# 04_MCU.net
KiCad netlist of a schematic drawn in Altium Designer
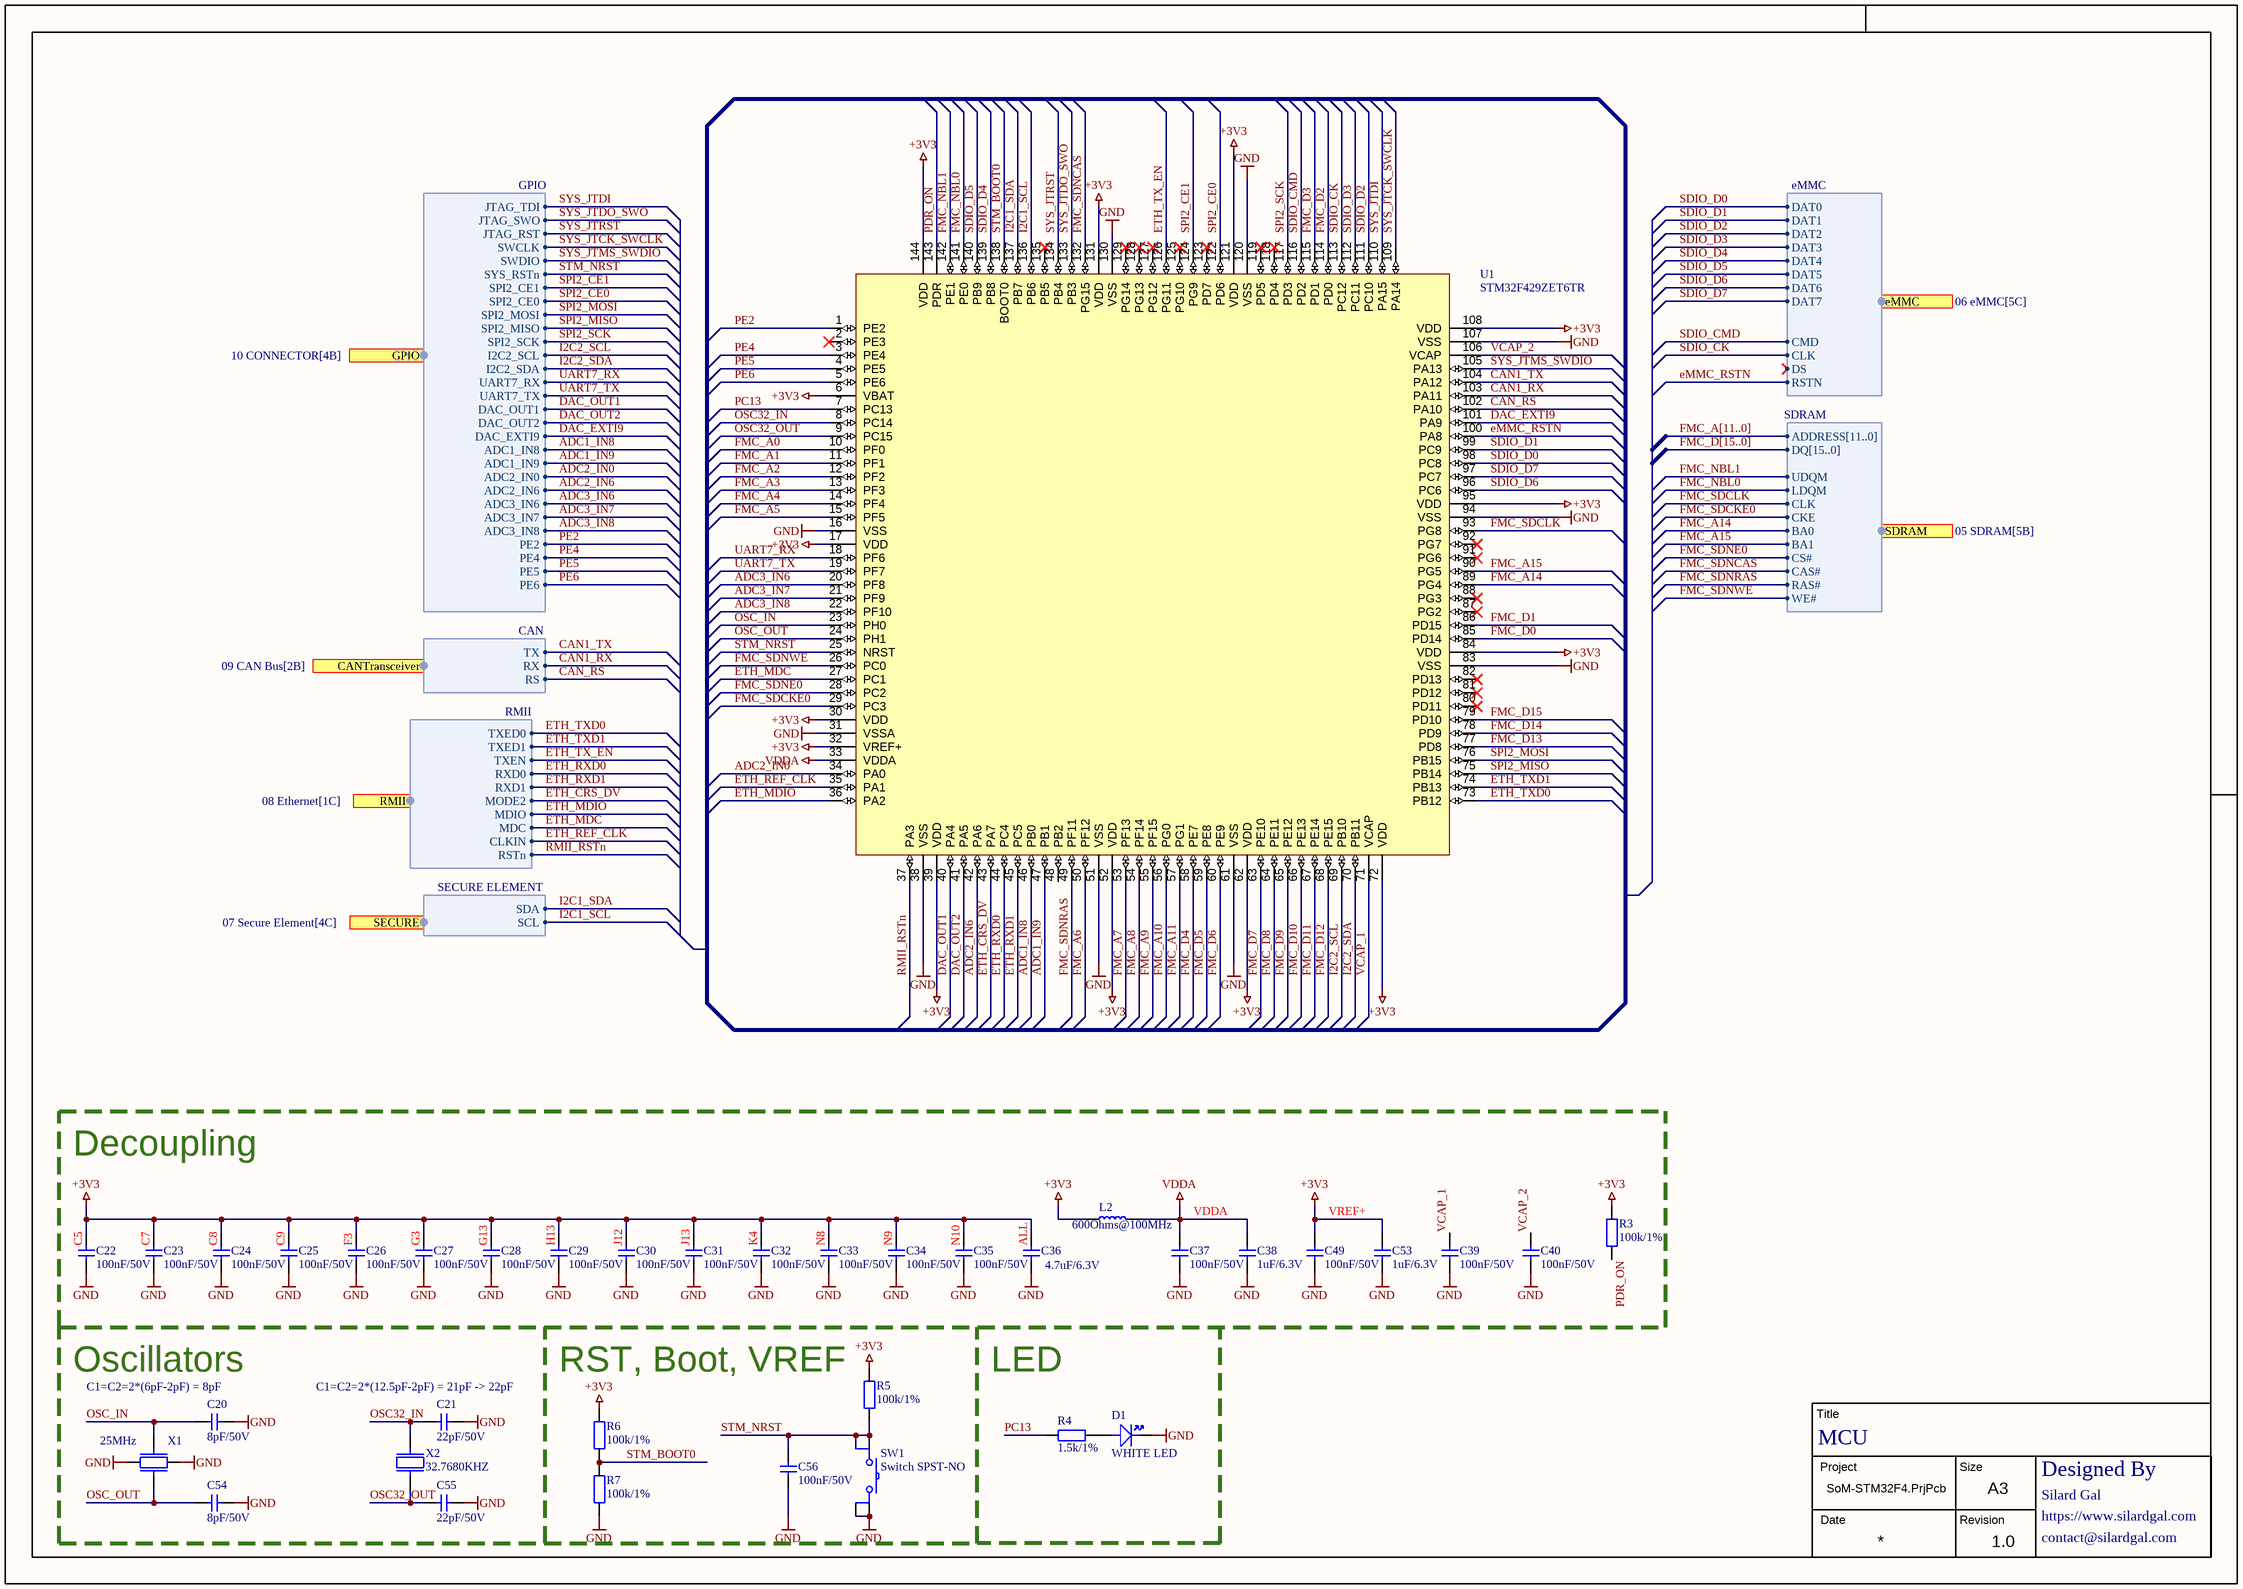
[diagram p0: 04 MCU.SchDoc]

(export (version "E")
  (design (tool "Eeschema 10.0.6"))
  (components
    (comp (ref "C20")
      (value "8pF/50V")
      (footprint "CAPC1005X06M-0402")
      (description "8 pF ±0.1pF 50V Ceramic Capacitor C0G, NP0 0402 (1005 Metric)")
      (fields (field (name "MPN") "GRM1555C1H8R0BA01D"))
      (libsource (lib "Symbol") (part "GRM1555C1H8R0BA01D"))
    )
    (comp (ref "C21")
      (value "22pF/50V")
      (footprint "CAPC1005X06M-0402")
      (description "22 pF ±5% 50V Ceramic Capacitor C0G, NP0 0402 (1005 Metric)")
      (fields (field (name "MPN") "GRM1555C1H220JA01D"))
      (libsource (lib "Symbol") (part "GRM1555C1H220JA01D"))
    )
    (comp (ref "C22")
      (value "100nF/50V")
      (footprint "CAPC1005X06M-0402")
      (description "0.1 µF ±10% 50V Ceramic Capacitor X7R 0402 (1005 Metric)")
      (fields (field (name "MPN") "GRM155R71H104KE14D"))
      (libsource (lib "Symbol") (part "GRM155R71H104KE14D"))
    )
    (comp (ref "C23")
      (value "100nF/50V")
      (footprint "CAPC1005X06M-0402")
      (description "0.1 µF ±10% 50V Ceramic Capacitor X7R 0402 (1005 Metric)")
      (fields (field (name "MPN") "GRM155R71H104KE14D"))
      (libsource (lib "Symbol") (part "GRM155R71H104KE14D"))
    )
    (comp (ref "C24")
      (value "100nF/50V")
      (footprint "CAPC1005X06M-0402")
      (description "0.1 µF ±10% 50V Ceramic Capacitor X7R 0402 (1005 Metric)")
      (fields (field (name "MPN") "GRM155R71H104KE14D"))
      (libsource (lib "Symbol") (part "GRM155R71H104KE14D"))
    )
    (comp (ref "C25")
      (value "100nF/50V")
      (footprint "CAPC1005X06M-0402")
      (description "0.1 µF ±10% 50V Ceramic Capacitor X7R 0402 (1005 Metric)")
      (fields (field (name "MPN") "GRM155R71H104KE14D"))
      (libsource (lib "Symbol") (part "GRM155R71H104KE14D"))
    )
    (comp (ref "C26")
      (value "100nF/50V")
      (footprint "CAPC1005X06M-0402")
      (description "0.1 µF ±10% 50V Ceramic Capacitor X7R 0402 (1005 Metric)")
      (fields (field (name "MPN") "GRM155R71H104KE14D"))
      (libsource (lib "Symbol") (part "GRM155R71H104KE14D"))
    )
    (comp (ref "C27")
      (value "100nF/50V")
      (footprint "CAPC1005X06M-0402")
      (description "0.1 µF ±10% 50V Ceramic Capacitor X7R 0402 (1005 Metric)")
      (fields (field (name "MPN") "GRM155R71H104KE14D"))
      (libsource (lib "Symbol") (part "GRM155R71H104KE14D"))
    )
    (comp (ref "C28")
      (value "100nF/50V")
      (footprint "CAPC1005X06M-0402")
      (description "0.1 µF ±10% 50V Ceramic Capacitor X7R 0402 (1005 Metric)")
      (fields (field (name "MPN") "GRM155R71H104KE14D"))
      (libsource (lib "Symbol") (part "GRM155R71H104KE14D"))
    )
    (comp (ref "C29")
      (value "100nF/50V")
      (footprint "CAPC1005X06M-0402")
      (description "0.1 µF ±10% 50V Ceramic Capacitor X7R 0402 (1005 Metric)")
      (fields (field (name "MPN") "GRM155R71H104KE14D"))
      (libsource (lib "Symbol") (part "GRM155R71H104KE14D"))
    )
    (comp (ref "C30")
      (value "100nF/50V")
      (footprint "CAPC1005X06M-0402")
      (description "0.1 µF ±10% 50V Ceramic Capacitor X7R 0402 (1005 Metric)")
      (fields (field (name "MPN") "GRM155R71H104KE14D"))
      (libsource (lib "Symbol") (part "GRM155R71H104KE14D"))
    )
    (comp (ref "C31")
      (value "100nF/50V")
      (footprint "CAPC1005X06M-0402")
      (description "0.1 µF ±10% 50V Ceramic Capacitor X7R 0402 (1005 Metric)")
      (fields (field (name "MPN") "GRM155R71H104KE14D"))
      (libsource (lib "Symbol") (part "GRM155R71H104KE14D"))
    )
    (comp (ref "C32")
      (value "100nF/50V")
      (footprint "CAPC1005X06M-0402")
      (description "0.1 µF ±10% 50V Ceramic Capacitor X7R 0402 (1005 Metric)")
      (fields (field (name "MPN") "GRM155R71H104KE14D"))
      (libsource (lib "Symbol") (part "GRM155R71H104KE14D"))
    )
    (comp (ref "C33")
      (value "100nF/50V")
      (footprint "CAPC1005X06M-0402")
      (description "0.1 µF ±10% 50V Ceramic Capacitor X7R 0402 (1005 Metric)")
      (fields (field (name "MPN") "GRM155R71H104KE14D"))
      (libsource (lib "Symbol") (part "GRM155R71H104KE14D"))
    )
    (comp (ref "C34")
      (value "100nF/50V")
      (footprint "CAPC1005X06M-0402")
      (description "0.1 µF ±10% 50V Ceramic Capacitor X7R 0402 (1005 Metric)")
      (fields (field (name "MPN") "GRM155R71H104KE14D"))
      (libsource (lib "Symbol") (part "GRM155R71H104KE14D"))
    )
    (comp (ref "C35")
      (value "100nF/50V")
      (footprint "CAPC1005X06M-0402")
      (description "0.1 µF ±10% 50V Ceramic Capacitor X7R 0402 (1005 Metric)")
      (fields (field (name "MPN") "GRM155R71H104KE14D"))
      (libsource (lib "Symbol") (part "GRM155R71H104KE14D"))
    )
    (comp (ref "C36")
      (value "4.7uF/6.3V")
      (footprint "CAPC1005X06M-0402")
      (description "4.7 µF ±20% 6.3V Ceramic Capacitor X5R 0402 (1005 Metric)")
      (fields (field (name "MPN") "GRM155R60J475ME47D"))
      (libsource (lib "Symbol") (part "GRM155R60J475ME47D"))
    )
    (comp (ref "C37")
      (value "100nF/50V")
      (footprint "CAPC1005X06M-0402")
      (description "0.1 µF ±10% 50V Ceramic Capacitor X7R 0402 (1005 Metric)")
      (fields (field (name "MPN") "GRM155R71H104KE14D"))
      (libsource (lib "Symbol") (part "GRM155R71H104KE14D"))
    )
    (comp (ref "C38")
      (value "1uF/6.3V")
      (footprint "CAPC1005X06M-0402")
      (description "1 µF ±10% 6.3V Ceramic Capacitor X7R 0402 (1005 Metric)")
      (fields (field (name "MPN") "GRM155R70J105KA12J"))
      (libsource (lib "Symbol") (part "GRM155R70J105KA12J"))
    )
    (comp (ref "C39")
      (value "100nF/50V")
      (footprint "CAPC1005X06M-0402")
      (description "0.1 µF ±10% 50V Ceramic Capacitor X7R 0402 (1005 Metric)")
      (fields (field (name "MPN") "GRM155R71H104KE14D"))
      (libsource (lib "Symbol") (part "GRM155R71H104KE14D"))
    )
    (comp (ref "C40")
      (value "100nF/50V")
      (footprint "CAPC1005X06M-0402")
      (description "0.1 µF ±10% 50V Ceramic Capacitor X7R 0402 (1005 Metric)")
      (fields (field (name "MPN") "GRM155R71H104KE14D"))
      (libsource (lib "Symbol") (part "GRM155R71H104KE14D"))
    )
    (comp (ref "C49")
      (value "100nF/50V")
      (footprint "CAPC1005X06M-0402")
      (description "0.1 µF ±10% 50V Ceramic Capacitor X7R 0402 (1005 Metric)")
      (fields (field (name "MPN") "GRM155R71H104KE14D"))
      (libsource (lib "Symbol") (part "GRM155R71H104KE14D"))
    )
    (comp (ref "C53")
      (value "1uF/6.3V")
      (footprint "CAPC1005X06M-0402")
      (description "1 µF ±10% 6.3V Ceramic Capacitor X7R 0402 (1005 Metric)")
      (fields (field (name "MPN") "GRM155R70J105KA12J"))
      (libsource (lib "Symbol") (part "GRM155R70J105KA12J"))
    )
    (comp (ref "C54")
      (value "8pF/50V")
      (footprint "CAPC1005X06M-0402")
      (description "8 pF ±0.1pF 50V Ceramic Capacitor C0G, NP0 0402 (1005 Metric)")
      (fields (field (name "MPN") "GRM1555C1H8R0BA01D"))
      (libsource (lib "Symbol") (part "GRM1555C1H8R0BA01D"))
    )
    (comp (ref "C55")
      (value "22pF/50V")
      (footprint "CAPC1005X06M-0402")
      (description "22 pF ±5% 50V Ceramic Capacitor C0G, NP0 0402 (1005 Metric)")
      (fields (field (name "MPN") "GRM1555C1H220JA01D"))
      (libsource (lib "Symbol") (part "GRM1555C1H220JA01D"))
    )
    (comp (ref "C56")
      (value "100nF/50V")
      (footprint "CAPC1005X06M-0402")
      (description "0.1 µF ±10% 50V Ceramic Capacitor X7R 0402 (1005 Metric)")
      (fields (field (name "MPN") "GRM155R71H104KE14D"))
      (libsource (lib "Symbol") (part "GRM155R71H104KE14D"))
    )
    (comp (ref "D1")
      (value "WHITE LED")
      (footprint "LED-0402")
      (description "White LED Indication - Discrete 3.1V 0402 (1005 Metric)")
      (fields (field (name "MPN") "QBLP595-IW-2897"))
      (libsource (lib "Symbol") (part "QBLP595-IW-2897"))
    )
    (comp (ref "L2")
      (value "600Ohms@100MHz")
      (footprint "INDC1005X06M-0402")
      (description "600 Ohms @ 100 MHz 1 Ferrite Bead 0402 (1005 Metric) 300mA 520mOhm")
      (fields (field (name "MPN") "BLM15AG601SN1D"))
      (libsource (lib "Symbol") (part "BLM15AG601SN1D"))
    )
    (comp (ref "R3")
      (value "100k/1%")
      (footprint "RESC1005X04M-0402")
      (description "100 kOhms ±1% 0.063W, 1/16W Chip Resistor 0402 (1005 Metric) Moisture Resistant Thick Film")
      (fields (field (name "MPN") "RC0402FR-07100KL"))
      (libsource (lib "Symbol") (part "RC0402FR-07100KL"))
    )
    (comp (ref "R4")
      (value "1.5k/1%")
      (footprint "RESC1005X04M-0402")
      (description "1.5 kOhms ±1% 0.063W, 1/16W Chip Resistor 0402 (1005 Metric) Moisture Resistant Thick Film")
      (fields (field (name "MPN") "RC0402FR-071K5L"))
      (libsource (lib "Symbol") (part "RC0402FR-071K5L"))
    )
    (comp (ref "R5")
      (value "100k/1%")
      (footprint "RESC1005X04M-0402")
      (description "100 kOhms ±1% 0.063W, 1/16W Chip Resistor 0402 (1005 Metric) Moisture Resistant Thick Film")
      (fields (field (name "MPN") "RC0402FR-07100KL"))
      (libsource (lib "Symbol") (part "RC0402FR-07100KL"))
    )
    (comp (ref "R6")
      (value "100k/1%")
      (footprint "RESC1005X04M-0402")
      (description "100 kOhms ±1% 0.063W, 1/16W Chip Resistor 0402 (1005 Metric) Moisture Resistant Thick Film")
      (fields (field (name "MPN") "RC0402FR-07100KL"))
      (libsource (lib "Symbol") (part "RC0402FR-07100KL"))
    )
    (comp (ref "R7")
      (value "100k/1%")
      (footprint "RESC1005X04M-0402")
      (description "100 kOhms ±1% 0.063W, 1/16W Chip Resistor 0402 (1005 Metric) Moisture Resistant Thick Film")
      (fields (field (name "MPN") "RC0402FR-07100KL"))
      (libsource (lib "Symbol") (part "RC0402FR-07100KL"))
    )
    (comp (ref "SW1")
      (value "Switch SPST-NO")
      (footprint "PTS815 SJM 250 SMTR LFS")
      (description "Tactile Switch SPST-NO Top Actuated Surface Mount")
      (fields (field (name "MPN") "PTS815 SJM 250 SMTR LFS"))
      (libsource (lib "Symbol") (part "PTS815 SJM 250 SMTR LFS"))
    )
    (comp (ref "U1")
      (value "STM32F429ZET6TR")
      (footprint "TSQFP50P2200X2200X160-144N")
      (libsource (lib "Symbol") (part "STM32F429ZET6TR"))
    )
    (comp (ref "X1")
      (value "25MHz")
      (footprint "4-SMD")
      (description "25 MHz ±30ppm Crystal 6pF 150 Ohms 4-SMD, No Lead")
      (fields (field (name "MPN") "XRCGB25M000F3M00R0"))
      (libsource (lib "Symbol") (part "XRCGB25M000F3M00R0"))
    )
    (comp (ref "X2")
      (value "32.7680KHZ")
      (footprint "2-SMD")
      (description "32.768 kHz ±20ppm Crystal 12.5pF 90 kOhms 2-SMD, No Lead")
      (fields (field (name "MPN") "ECS-.327-12.5-16-TR"))
      (libsource (lib "Symbol") (part "ECS-.327-12.5-16-TR"))
    )
  )
  (nets
    (net (code "8") (name "+3V3") (class "Default")
      (node (ref "C22") (pin "2") (pinfunction "2_2") (pintype "passive"))
      (node (ref "C23") (pin "2") (pinfunction "2_2") (pintype "passive"))
      (node (ref "C24") (pin "2") (pinfunction "2_2") (pintype "passive"))
      (node (ref "C25") (pin "2") (pinfunction "2_2") (pintype "passive"))
      (node (ref "C26") (pin "2") (pinfunction "2_2") (pintype "passive"))
      (node (ref "C27") (pin "2") (pinfunction "2_2") (pintype "passive"))
      (node (ref "C28") (pin "2") (pinfunction "2_2") (pintype "passive"))
      (node (ref "C29") (pin "2") (pinfunction "2_2") (pintype "passive"))
      (node (ref "C30") (pin "2") (pinfunction "2_2") (pintype "passive"))
      (node (ref "C31") (pin "2") (pinfunction "2_2") (pintype "passive"))
      (node (ref "C32") (pin "2") (pinfunction "2_2") (pintype "passive"))
      (node (ref "C33") (pin "2") (pinfunction "2_2") (pintype "passive"))
      (node (ref "C34") (pin "2") (pinfunction "2_2") (pintype "passive"))
      (node (ref "C35") (pin "2") (pinfunction "2_2") (pintype "passive"))
      (node (ref "C36") (pin "2") (pinfunction "2_2") (pintype "passive"))
      (node (ref "C49") (pin "2") (pinfunction "2_2") (pintype "passive"))
      (node (ref "C53") (pin "2") (pinfunction "2_2") (pintype "passive"))
      (node (ref "L2") (pin "1") (pinfunction "1_1") (pintype "passive"))
      (node (ref "R3") (pin "1") (pinfunction "1_1") (pintype "passive"))
      (node (ref "R5") (pin "1") (pinfunction "1_1") (pintype "passive"))
      (node (ref "R6") (pin "1") (pinfunction "1_1") (pintype "passive"))
      (node (ref "U1") (pin "108") (pinfunction "VDD_108") (pintype "power_in"))
      (node (ref "U1") (pin "121") (pinfunction "VDD_121") (pintype "power_in"))
      (node (ref "U1") (pin "131") (pinfunction "VDD_131") (pintype "power_in"))
      (node (ref "U1") (pin "144") (pinfunction "VDD_144") (pintype "power_in"))
      (node (ref "U1") (pin "17") (pinfunction "VDD_17") (pintype "power_in"))
      (node (ref "U1") (pin "30") (pinfunction "VDD_30") (pintype "power_in"))
      (node (ref "U1") (pin "32") (pinfunction "VREF+_32") (pintype "power_in"))
      (node (ref "U1") (pin "39") (pinfunction "VDD_39") (pintype "power_in"))
      (node (ref "U1") (pin "52") (pinfunction "VDD_52") (pintype "power_in"))
      (node (ref "U1") (pin "6") (pinfunction "VBAT_6") (pintype "power_in"))
      (node (ref "U1") (pin "62") (pinfunction "VDD_62") (pintype "power_in"))
      (node (ref "U1") (pin "72") (pinfunction "VDD_72") (pintype "power_in"))
      (node (ref "U1") (pin "84") (pinfunction "VDD_84") (pintype "power_in"))
      (node (ref "U1") (pin "95") (pinfunction "VDD_95") (pintype "power_in"))
    )
    (net (code "9") (name "/ADC1_IN8") (class "Default")
      (node (ref "U1") (pin "46") (pinfunction "PB0_46") (pintype "bidirectional"))
    )
    (net (code "10") (name "/ADC1_IN9") (class "Default")
      (node (ref "U1") (pin "47") (pinfunction "PB1_47") (pintype "bidirectional"))
    )
    (net (code "11") (name "/ADC2_IN0") (class "Default")
      (node (ref "U1") (pin "34") (pinfunction "PA0_34") (pintype "bidirectional"))
    )
    (net (code "12") (name "/ADC2_IN6") (class "Default")
      (node (ref "U1") (pin "42") (pinfunction "PA6_42") (pintype "bidirectional"))
    )
    (net (code "13") (name "/ADC3_IN6") (class "Default")
      (node (ref "U1") (pin "20") (pinfunction "PF8_20") (pintype "bidirectional"))
    )
    (net (code "14") (name "/ADC3_IN7") (class "Default")
      (node (ref "U1") (pin "21") (pinfunction "PF9_21") (pintype "bidirectional"))
    )
    (net (code "15") (name "/ADC3_IN8") (class "Default")
      (node (ref "U1") (pin "22") (pinfunction "PF10_22") (pintype "bidirectional"))
    )
    (net (code "16") (name "/CAN1_RX") (class "Default")
      (node (ref "U1") (pin "103") (pinfunction "PA11_103") (pintype "bidirectional"))
    )
    (net (code "17") (name "/CAN1_TX") (class "Default")
      (node (ref "U1") (pin "104") (pinfunction "PA12_104") (pintype "bidirectional"))
    )
    (net (code "18") (name "/CAN_RS") (class "Default")
      (node (ref "U1") (pin "102") (pinfunction "PA10_102") (pintype "bidirectional"))
    )
    (net (code "19") (name "/DAC_EXTI9") (class "Default")
      (node (ref "U1") (pin "101") (pinfunction "PA9_101") (pintype "bidirectional"))
    )
    (net (code "20") (name "/DAC_OUT1") (class "Default")
      (node (ref "U1") (pin "40") (pinfunction "PA4_40") (pintype "bidirectional"))
    )
    (net (code "21") (name "/DAC_OUT2") (class "Default")
      (node (ref "U1") (pin "41") (pinfunction "PA5_41") (pintype "bidirectional"))
    )
    (net (code "22") (name "/ETH_CRS_DV") (class "Default")
      (node (ref "U1") (pin "43") (pinfunction "PA7_43") (pintype "bidirectional"))
    )
    (net (code "23") (name "/ETH_MDC") (class "Default")
      (node (ref "U1") (pin "27") (pinfunction "PC1_27") (pintype "bidirectional"))
    )
    (net (code "24") (name "/ETH_MDIO") (class "Default")
      (node (ref "U1") (pin "36") (pinfunction "PA2_36") (pintype "bidirectional"))
    )
    (net (code "25") (name "/ETH_REF_CLK") (class "Default")
      (node (ref "U1") (pin "35") (pinfunction "PA1_35") (pintype "bidirectional"))
    )
    (net (code "26") (name "/ETH_RXD0") (class "Default")
      (node (ref "U1") (pin "44") (pinfunction "PC4_44") (pintype "bidirectional"))
    )
    (net (code "27") (name "/ETH_RXD1") (class "Default")
      (node (ref "U1") (pin "45") (pinfunction "PC5_45") (pintype "bidirectional"))
    )
    (net (code "28") (name "/ETH_TXD0") (class "Default")
      (node (ref "U1") (pin "73") (pinfunction "PB12_73") (pintype "bidirectional"))
    )
    (net (code "29") (name "/ETH_TXD1") (class "Default")
      (node (ref "U1") (pin "74") (pinfunction "PB13_74") (pintype "bidirectional"))
    )
    (net (code "30") (name "/ETH_TX_EN") (class "Default")
      (node (ref "U1") (pin "126") (pinfunction "PG11_126") (pintype "bidirectional"))
    )
    (net (code "31") (name "/FMC_A0") (class "Default")
      (node (ref "U1") (pin "10") (pinfunction "PF0_10") (pintype "bidirectional"))
    )
    (net (code "32") (name "/FMC_A1") (class "Default")
      (node (ref "U1") (pin "11") (pinfunction "PF1_11") (pintype "bidirectional"))
    )
    (net (code "33") (name "/FMC_A2") (class "Default")
      (node (ref "U1") (pin "12") (pinfunction "PF2_12") (pintype "bidirectional"))
    )
    (net (code "34") (name "/FMC_A3") (class "Default")
      (node (ref "U1") (pin "13") (pinfunction "PF3_13") (pintype "bidirectional"))
    )
    (net (code "35") (name "/FMC_A4") (class "Default")
      (node (ref "U1") (pin "14") (pinfunction "PF4_14") (pintype "bidirectional"))
    )
    (net (code "36") (name "/FMC_A5") (class "Default")
      (node (ref "U1") (pin "15") (pinfunction "PF5_15") (pintype "bidirectional"))
    )
    (net (code "37") (name "/FMC_A6") (class "Default")
      (node (ref "U1") (pin "50") (pinfunction "PF12_50") (pintype "bidirectional"))
    )
    (net (code "38") (name "/FMC_A7") (class "Default")
      (node (ref "U1") (pin "53") (pinfunction "PF13_53") (pintype "bidirectional"))
    )
    (net (code "39") (name "/FMC_A8") (class "Default")
      (node (ref "U1") (pin "54") (pinfunction "PF14_54") (pintype "bidirectional"))
    )
    (net (code "40") (name "/FMC_A9") (class "Default")
      (node (ref "U1") (pin "55") (pinfunction "PF15_55") (pintype "bidirectional"))
    )
    (net (code "41") (name "/FMC_A10") (class "Default")
      (node (ref "U1") (pin "56") (pinfunction "PG0_56") (pintype "bidirectional"))
    )
    (net (code "42") (name "/FMC_A11") (class "Default")
      (node (ref "U1") (pin "57") (pinfunction "PG1_57") (pintype "bidirectional"))
    )
    (net (code "43") (name "/FMC_A14") (class "Default")
      (node (ref "U1") (pin "89") (pinfunction "PG4_89") (pintype "bidirectional"))
    )
    (net (code "44") (name "/FMC_A15") (class "Default")
      (node (ref "U1") (pin "90") (pinfunction "PG5_90") (pintype "bidirectional"))
    )
    (net (code "46") (name "/FMC_D0") (class "Default")
      (node (ref "U1") (pin "85") (pinfunction "PD14_85") (pintype "bidirectional"))
    )
    (net (code "47") (name "/FMC_D1") (class "Default")
      (node (ref "U1") (pin "86") (pinfunction "PD15_86") (pintype "bidirectional"))
    )
    (net (code "48") (name "/FMC_D2") (class "Default")
      (node (ref "U1") (pin "114") (pinfunction "PD0_114") (pintype "bidirectional"))
    )
    (net (code "49") (name "/FMC_D3") (class "Default")
      (node (ref "U1") (pin "115") (pinfunction "PD1_115") (pintype "bidirectional"))
    )
    (net (code "50") (name "/FMC_D4") (class "Default")
      (node (ref "U1") (pin "58") (pinfunction "PE7_58") (pintype "bidirectional"))
    )
    (net (code "51") (name "/FMC_D5") (class "Default")
      (node (ref "U1") (pin "59") (pinfunction "PE8_59") (pintype "bidirectional"))
    )
    (net (code "52") (name "/FMC_D6") (class "Default")
      (node (ref "U1") (pin "60") (pinfunction "PE9_60") (pintype "bidirectional"))
    )
    (net (code "53") (name "/FMC_D7") (class "Default")
      (node (ref "U1") (pin "63") (pinfunction "PE10_63") (pintype "bidirectional"))
    )
    (net (code "54") (name "/FMC_D8") (class "Default")
      (node (ref "U1") (pin "64") (pinfunction "PE11_64") (pintype "bidirectional"))
    )
    (net (code "55") (name "/FMC_D9") (class "Default")
      (node (ref "U1") (pin "65") (pinfunction "PE12_65") (pintype "bidirectional"))
    )
    (net (code "56") (name "/FMC_D10") (class "Default")
      (node (ref "U1") (pin "66") (pinfunction "PE13_66") (pintype "bidirectional"))
    )
    (net (code "57") (name "/FMC_D11") (class "Default")
      (node (ref "U1") (pin "67") (pinfunction "PE14_67") (pintype "bidirectional"))
    )
    (net (code "58") (name "/FMC_D12") (class "Default")
      (node (ref "U1") (pin "68") (pinfunction "PE15_68") (pintype "bidirectional"))
    )
    (net (code "59") (name "/FMC_D13") (class "Default")
      (node (ref "U1") (pin "77") (pinfunction "PD8_77") (pintype "bidirectional"))
    )
    (net (code "60") (name "/FMC_D14") (class "Default")
      (node (ref "U1") (pin "78") (pinfunction "PD9_78") (pintype "bidirectional"))
    )
    (net (code "61") (name "/FMC_D15") (class "Default")
      (node (ref "U1") (pin "79") (pinfunction "PD10_79") (pintype "bidirectional"))
    )
    (net (code "62") (name "/FMC_NBL0") (class "Default")
      (node (ref "U1") (pin "141") (pinfunction "PE0_141") (pintype "bidirectional"))
    )
    (net (code "63") (name "/FMC_NBL1") (class "Default")
      (node (ref "U1") (pin "142") (pinfunction "PE1_142") (pintype "bidirectional"))
    )
    (net (code "64") (name "/FMC_SDCKE0") (class "Default")
      (node (ref "U1") (pin "29") (pinfunction "PC3_29") (pintype "bidirectional"))
    )
    (net (code "65") (name "/FMC_SDCLK") (class "Default")
      (node (ref "U1") (pin "93") (pinfunction "PG8_93") (pintype "bidirectional"))
    )
    (net (code "66") (name "/FMC_SDNCAS") (class "Default")
      (node (ref "U1") (pin "132") (pinfunction "PG15_132") (pintype "bidirectional"))
    )
    (net (code "67") (name "/FMC_SDNE0") (class "Default")
      (node (ref "U1") (pin "28") (pinfunction "PC2_28") (pintype "bidirectional"))
    )
    (net (code "68") (name "/FMC_SDNRAS") (class "Default")
      (node (ref "U1") (pin "49") (pinfunction "PF11_49") (pintype "bidirectional"))
    )
    (net (code "69") (name "/FMC_SDNWE") (class "Default")
      (node (ref "U1") (pin "26") (pinfunction "PC0_26") (pintype "bidirectional"))
    )
    (net (code "70") (name "/I2C1_SCL") (class "Default")
      (node (ref "U1") (pin "136") (pinfunction "PB6_136") (pintype "bidirectional"))
    )
    (net (code "71") (name "/I2C1_SDA") (class "Default")
      (node (ref "U1") (pin "137") (pinfunction "PB7_137") (pintype "bidirectional"))
    )
    (net (code "72") (name "/I2C2_SCL") (class "Default")
      (node (ref "U1") (pin "69") (pinfunction "PB10_69") (pintype "bidirectional"))
    )
    (net (code "73") (name "/I2C2_SDA") (class "Default")
      (node (ref "U1") (pin "70") (pinfunction "PB11_70") (pintype "bidirectional"))
    )
    (net (code "74") (name "/OSC32_IN") (class "Default")
      (node (ref "C21") (pin "1") (pinfunction "1_1") (pintype "passive"))
      (node (ref "U1") (pin "8") (pinfunction "PC14_8") (pintype "bidirectional"))
      (node (ref "X2") (pin "2") (pinfunction "2_2") (pintype "passive"))
    )
    (net (code "75") (name "/OSC32_OUT") (class "Default")
      (node (ref "C55") (pin "1") (pinfunction "1_1") (pintype "passive"))
      (node (ref "U1") (pin "9") (pinfunction "PC15_9") (pintype "bidirectional"))
      (node (ref "X2") (pin "1") (pinfunction "1_1") (pintype "passive"))
    )
    (net (code "76") (name "/OSC_IN") (class "Default")
      (node (ref "C20") (pin "1") (pinfunction "1_1") (pintype "passive"))
      (node (ref "U1") (pin "23") (pinfunction "PH0_23") (pintype "bidirectional"))
      (node (ref "X1") (pin "3") (pinfunction "3_3") (pintype "passive"))
    )
    (net (code "77") (name "/OSC_OUT") (class "Default")
      (node (ref "C54") (pin "1") (pinfunction "1_1") (pintype "passive"))
      (node (ref "U1") (pin "24") (pinfunction "PH1_24") (pintype "bidirectional"))
      (node (ref "X1") (pin "1") (pinfunction "1_1") (pintype "passive"))
    )
    (net (code "78") (name "/PC13") (class "Default")
      (node (ref "R4") (pin "1") (pinfunction "1_1") (pintype "passive"))
      (node (ref "U1") (pin "7") (pinfunction "PC13_7") (pintype "bidirectional"))
    )
    (net (code "79") (name "/PDR_ON") (class "Default")
      (node (ref "R3") (pin "2") (pinfunction "2_2") (pintype "passive"))
      (node (ref "U1") (pin "143") (pinfunction "PDR_143") (pintype "power_in"))
    )
    (net (code "80") (name "/PE2") (class "Default")
      (node (ref "U1") (pin "1") (pinfunction "PE2_1") (pintype "bidirectional"))
    )
    (net (code "81") (name "/PE4") (class "Default")
      (node (ref "U1") (pin "3") (pinfunction "PE4_3") (pintype "bidirectional"))
    )
    (net (code "82") (name "/PE5") (class "Default")
      (node (ref "U1") (pin "4") (pinfunction "PE5_4") (pintype "bidirectional"))
    )
    (net (code "83") (name "/PE6") (class "Default")
      (node (ref "U1") (pin "5") (pinfunction "PE6_5") (pintype "bidirectional"))
    )
    (net (code "84") (name "/RMII_RSTn") (class "Default")
      (node (ref "U1") (pin "37") (pinfunction "PA3_37") (pintype "bidirectional"))
    )
    (net (code "85") (name "/SDIO_CK") (class "Default")
      (node (ref "U1") (pin "113") (pinfunction "PC12_113") (pintype "bidirectional"))
    )
    (net (code "86") (name "/SDIO_CMD") (class "Default")
      (node (ref "U1") (pin "116") (pinfunction "PD2_116") (pintype "bidirectional"))
    )
    (net (code "87") (name "/SDIO_D0") (class "Default")
      (node (ref "U1") (pin "98") (pinfunction "PC8_98") (pintype "bidirectional"))
    )
    (net (code "88") (name "/SDIO_D1") (class "Default")
      (node (ref "U1") (pin "99") (pinfunction "PC9_99") (pintype "bidirectional"))
    )
    (net (code "89") (name "/SDIO_D2") (class "Default")
      (node (ref "U1") (pin "111") (pinfunction "PC10_111") (pintype "bidirectional"))
    )
    (net (code "90") (name "/SDIO_D3") (class "Default")
      (node (ref "U1") (pin "112") (pinfunction "PC11_112") (pintype "bidirectional"))
    )
    (net (code "91") (name "/SDIO_D4") (class "Default")
      (node (ref "U1") (pin "139") (pinfunction "PB8_139") (pintype "bidirectional"))
    )
    (net (code "92") (name "/SDIO_D5") (class "Default")
      (node (ref "U1") (pin "140") (pinfunction "PB9_140") (pintype "bidirectional"))
    )
    (net (code "93") (name "/SDIO_D6") (class "Default")
      (node (ref "U1") (pin "96") (pinfunction "PC6_96") (pintype "bidirectional"))
    )
    (net (code "94") (name "/SDIO_D7") (class "Default")
      (node (ref "U1") (pin "97") (pinfunction "PC7_97") (pintype "bidirectional"))
    )
    (net (code "96") (name "/SPI2_CE0") (class "Default")
      (node (ref "U1") (pin "122") (pinfunction "PD6_122") (pintype "bidirectional"))
    )
    (net (code "97") (name "/SPI2_CE1") (class "Default")
      (node (ref "U1") (pin "124") (pinfunction "PG9_124") (pintype "bidirectional"))
    )
    (net (code "98") (name "/SPI2_MISO") (class "Default")
      (node (ref "U1") (pin "75") (pinfunction "PB14_75") (pintype "bidirectional"))
    )
    (net (code "99") (name "/SPI2_MOSI") (class "Default")
      (node (ref "U1") (pin "76") (pinfunction "PB15_76") (pintype "bidirectional"))
    )
    (net (code "100") (name "/SPI2_SCK") (class "Default")
      (node (ref "U1") (pin "117") (pinfunction "PD3_117") (pintype "bidirectional"))
    )
    (net (code "101") (name "/STM_BOOT0") (class "Default")
      (node (ref "R6") (pin "2") (pinfunction "2_2") (pintype "passive"))
      (node (ref "R7") (pin "2") (pinfunction "2_2") (pintype "passive"))
      (node (ref "U1") (pin "138") (pinfunction "BOOT0_138") (pintype "bidirectional"))
    )
    (net (code "102") (name "/STM_NRST") (class "Default")
      (node (ref "C56") (pin "2") (pinfunction "2_2") (pintype "passive"))
      (node (ref "R5") (pin "2") (pinfunction "2_2") (pintype "passive"))
      (node (ref "SW1") (pin "1") (pinfunction "1_1") (pintype "passive"))
      (node (ref "SW1") (pin "2") (pinfunction "2_2") (pintype "passive"))
      (node (ref "U1") (pin "25") (pinfunction "NRST_25") (pintype "bidirectional"))
    )
    (net (code "103") (name "/SYS_JTCK_SWCLK") (class "Default")
      (node (ref "U1") (pin "109") (pinfunction "PA14_109") (pintype "bidirectional"))
    )
    (net (code "104") (name "/SYS_JTDI") (class "Default")
      (node (ref "U1") (pin "110") (pinfunction "PA15_110") (pintype "bidirectional"))
    )
    (net (code "105") (name "/SYS_JTDO_SWO") (class "Default")
      (node (ref "U1") (pin "133") (pinfunction "PB3_133") (pintype "bidirectional"))
    )
    (net (code "106") (name "/SYS_JTMS_SWDIO") (class "Default")
      (node (ref "U1") (pin "105") (pinfunction "PA13_105") (pintype "bidirectional"))
    )
    (net (code "107") (name "/SYS_JTRST") (class "Default")
      (node (ref "U1") (pin "134") (pinfunction "PB4_134") (pintype "bidirectional"))
    )
    (net (code "108") (name "/UART7_RX") (class "Default")
      (node (ref "U1") (pin "18") (pinfunction "PF6_18") (pintype "bidirectional"))
    )
    (net (code "109") (name "/UART7_TX") (class "Default")
      (node (ref "U1") (pin "19") (pinfunction "PF7_19") (pintype "bidirectional"))
    )
    (net (code "110") (name "/VCAP_1") (class "Default")
      (node (ref "C39") (pin "2") (pinfunction "2_2") (pintype "passive"))
      (node (ref "U1") (pin "71") (pinfunction "VCAP_71") (pintype "power_in"))
    )
    (net (code "111") (name "/VCAP_2") (class "Default")
      (node (ref "C40") (pin "2") (pinfunction "2_2") (pintype "passive"))
      (node (ref "U1") (pin "106") (pinfunction "VCAP_106") (pintype "power_in"))
    )
    (net (code "112") (name "/eMMC_RSTN") (class "Default")
      (node (ref "U1") (pin "100") (pinfunction "PA8_100") (pintype "bidirectional"))
    )
    (net (code "119") (name "GND") (class "Default")
      (node (ref "C20") (pin "2") (pinfunction "2_2") (pintype "passive"))
      (node (ref "C21") (pin "2") (pinfunction "2_2") (pintype "passive"))
      (node (ref "C22") (pin "1") (pinfunction "1_1") (pintype "passive"))
      (node (ref "C23") (pin "1") (pinfunction "1_1") (pintype "passive"))
      (node (ref "C24") (pin "1") (pinfunction "1_1") (pintype "passive"))
      (node (ref "C25") (pin "1") (pinfunction "1_1") (pintype "passive"))
      (node (ref "C26") (pin "1") (pinfunction "1_1") (pintype "passive"))
      (node (ref "C27") (pin "1") (pinfunction "1_1") (pintype "passive"))
      (node (ref "C28") (pin "1") (pinfunction "1_1") (pintype "passive"))
      (node (ref "C29") (pin "1") (pinfunction "1_1") (pintype "passive"))
      (node (ref "C30") (pin "1") (pinfunction "1_1") (pintype "passive"))
      (node (ref "C31") (pin "1") (pinfunction "1_1") (pintype "passive"))
      (node (ref "C32") (pin "1") (pinfunction "1_1") (pintype "passive"))
      (node (ref "C33") (pin "1") (pinfunction "1_1") (pintype "passive"))
      (node (ref "C34") (pin "1") (pinfunction "1_1") (pintype "passive"))
      (node (ref "C35") (pin "1") (pinfunction "1_1") (pintype "passive"))
      (node (ref "C36") (pin "1") (pinfunction "1_1") (pintype "passive"))
      (node (ref "C37") (pin "1") (pinfunction "1_1") (pintype "passive"))
      (node (ref "C38") (pin "1") (pinfunction "1_1") (pintype "passive"))
      (node (ref "C39") (pin "1") (pinfunction "1_1") (pintype "passive"))
      (node (ref "C40") (pin "1") (pinfunction "1_1") (pintype "passive"))
      (node (ref "C49") (pin "1") (pinfunction "1_1") (pintype "passive"))
      (node (ref "C53") (pin "1") (pinfunction "1_1") (pintype "passive"))
      (node (ref "C54") (pin "2") (pinfunction "2_2") (pintype "passive"))
      (node (ref "C55") (pin "2") (pinfunction "2_2") (pintype "passive"))
      (node (ref "C56") (pin "1") (pinfunction "1_1") (pintype "passive"))
      (node (ref "D1") (pin "1") (pinfunction "1_1") (pintype "passive"))
      (node (ref "R7") (pin "1") (pinfunction "1_1") (pintype "passive"))
      (node (ref "SW1") (pin "3") (pinfunction "3_3") (pintype "passive"))
      (node (ref "SW1") (pin "4") (pinfunction "4_4") (pintype "passive"))
      (node (ref "U1") (pin "107") (pinfunction "VSS_107") (pintype "power_in"))
      (node (ref "U1") (pin "120") (pinfunction "VSS_120") (pintype "power_in"))
      (node (ref "U1") (pin "130") (pinfunction "VSS_130") (pintype "power_in"))
      (node (ref "U1") (pin "16") (pinfunction "VSS_16") (pintype "power_in"))
      (node (ref "U1") (pin "31") (pinfunction "VSSA_31") (pintype "power_in"))
      (node (ref "U1") (pin "38") (pinfunction "VSS_38") (pintype "power_in"))
      (node (ref "U1") (pin "51") (pinfunction "VSS_51") (pintype "power_in"))
      (node (ref "U1") (pin "61") (pinfunction "VSS_61") (pintype "power_in"))
      (node (ref "U1") (pin "83") (pinfunction "VSS_83") (pintype "power_in"))
      (node (ref "U1") (pin "94") (pinfunction "VSS_94") (pintype "power_in"))
      (node (ref "X1") (pin "2") (pinfunction "2_2") (pintype "passive"))
      (node (ref "X1") (pin "4") (pinfunction "4_4") (pintype "passive"))
    )
    (net (code "120") (name "Net-(D1-Pad2)") (class "Default")
      (node (ref "D1") (pin "2") (pinfunction "2_2") (pintype "passive"))
      (node (ref "R4") (pin "2") (pinfunction "2_2") (pintype "passive"))
    )
    (net (code "121") (name "VDDA") (class "Default")
      (node (ref "C37") (pin "2") (pinfunction "2_2") (pintype "passive"))
      (node (ref "C38") (pin "2") (pinfunction "2_2") (pintype "passive"))
      (node (ref "L2") (pin "2") (pinfunction "2_2") (pintype "passive"))
      (node (ref "U1") (pin "33") (pinfunction "VDDA_33") (pintype "power_in"))
    )
    (net (code "122") (name "unconnected-(U1-PB2-Pad48)") (class "Default")
      (node (ref "U1") (pin "48") (pinfunction "PB2_48") (pintype "bidirectional"))
    )
    (net (code "123") (name "unconnected-(U1-PB5-Pad135)") (class "Default")
      (node (ref "U1") (pin "135") (pinfunction "PB5_135") (pintype "bidirectional+no_connect"))
    )
    (net (code "124") (name "unconnected-(U1-PD4-Pad118)") (class "Default")
      (node (ref "U1") (pin "118") (pinfunction "PD4_118") (pintype "bidirectional+no_connect"))
    )
    (net (code "125") (name "unconnected-(U1-PD5-Pad119)") (class "Default")
      (node (ref "U1") (pin "119") (pinfunction "PD5_119") (pintype "bidirectional+no_connect"))
    )
    (net (code "126") (name "unconnected-(U1-PD7-Pad123)") (class "Default")
      (node (ref "U1") (pin "123") (pinfunction "PD7_123") (pintype "bidirectional+no_connect"))
    )
    (net (code "127") (name "unconnected-(U1-PD11-Pad80)") (class "Default")
      (node (ref "U1") (pin "80") (pinfunction "PD11_80") (pintype "bidirectional+no_connect"))
    )
    (net (code "128") (name "unconnected-(U1-PD12-Pad81)") (class "Default")
      (node (ref "U1") (pin "81") (pinfunction "PD12_81") (pintype "bidirectional+no_connect"))
    )
    (net (code "129") (name "unconnected-(U1-PD13-Pad82)") (class "Default")
      (node (ref "U1") (pin "82") (pinfunction "PD13_82") (pintype "bidirectional+no_connect"))
    )
    (net (code "130") (name "unconnected-(U1-PE3-Pad2)") (class "Default")
      (node (ref "U1") (pin "2") (pinfunction "PE3_2") (pintype "bidirectional+no_connect"))
    )
    (net (code "131") (name "unconnected-(U1-PG2-Pad87)") (class "Default")
      (node (ref "U1") (pin "87") (pinfunction "PG2_87") (pintype "bidirectional+no_connect"))
    )
    (net (code "132") (name "unconnected-(U1-PG3-Pad88)") (class "Default")
      (node (ref "U1") (pin "88") (pinfunction "PG3_88") (pintype "bidirectional+no_connect"))
    )
    (net (code "133") (name "unconnected-(U1-PG6-Pad91)") (class "Default")
      (node (ref "U1") (pin "91") (pinfunction "PG6_91") (pintype "bidirectional+no_connect"))
    )
    (net (code "134") (name "unconnected-(U1-PG7-Pad92)") (class "Default")
      (node (ref "U1") (pin "92") (pinfunction "PG7_92") (pintype "bidirectional+no_connect"))
    )
    (net (code "135") (name "unconnected-(U1-PG10-Pad125)") (class "Default")
      (node (ref "U1") (pin "125") (pinfunction "PG10_125") (pintype "bidirectional+no_connect"))
    )
    (net (code "136") (name "unconnected-(U1-PG12-Pad127)") (class "Default")
      (node (ref "U1") (pin "127") (pinfunction "PG12_127") (pintype "bidirectional+no_connect"))
    )
    (net (code "137") (name "unconnected-(U1-PG13-Pad128)") (class "Default")
      (node (ref "U1") (pin "128") (pinfunction "PG13_128") (pintype "bidirectional+no_connect"))
    )
    (net (code "138") (name "unconnected-(U1-PG14-Pad129)") (class "Default")
      (node (ref "U1") (pin "129") (pinfunction "PG14_129") (pintype "bidirectional+no_connect"))
    )
  )
)
